# controller.net
KiCad netlist of a schematic drawn in EAGLE
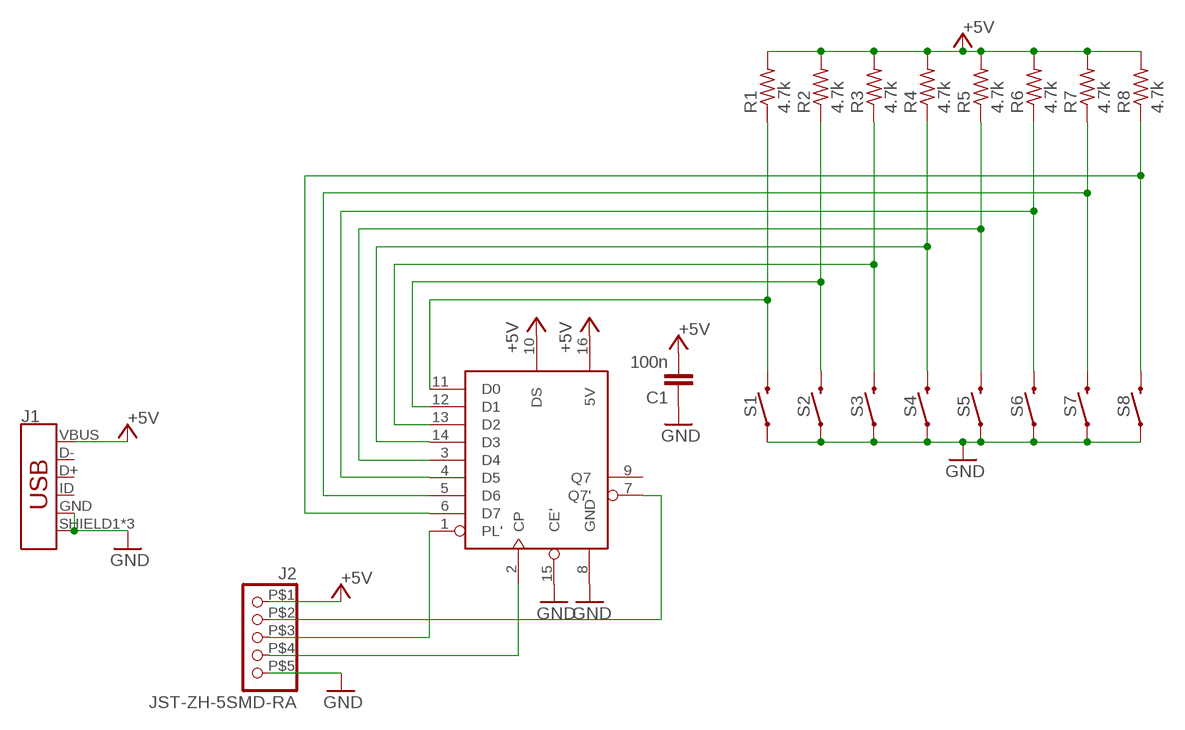
[diagram p0: schematic, sheet 1]

(export (version "E")
  (design (tool "Eeschema 10.0.6"))
  (components
    (comp (ref "C1")
      (value "100n")
      (footprint "eagle-import:C0603")
      (libsource (lib "eagle-import") (part "C-EUC0603"))
    )
    (comp (ref "J1")
      (value "USB_MICRO-B_FEMALE-SMT")
      (footprint "eagle-import:USB-B-MICRO-SMD")
      (libsource (lib "eagle-import") (part "USB_MICRO-B_FEMALE-SMT"))
    )
    (comp (ref "J2")
      (value "JST-ZH-5SMD-RA")
      (footprint "eagle-import:JST-ZH-5-SMD-RA")
      (libsource (lib "eagle-import") (part "JST-ZH-5SMD-RA"))
    )
    (comp (ref "R1")
      (value "4.7k")
      (footprint "eagle-import:R0603")
      (libsource (lib "eagle-import") (part "R-US_R0603"))
    )
    (comp (ref "R2")
      (value "4.7k")
      (footprint "eagle-import:R0603")
      (libsource (lib "eagle-import") (part "R-US_R0603"))
    )
    (comp (ref "R3")
      (value "4.7k")
      (footprint "eagle-import:R0603")
      (libsource (lib "eagle-import") (part "R-US_R0603"))
    )
    (comp (ref "R4")
      (value "4.7k")
      (footprint "eagle-import:R0603")
      (libsource (lib "eagle-import") (part "R-US_R0603"))
    )
    (comp (ref "R5")
      (value "4.7k")
      (footprint "eagle-import:R0603")
      (libsource (lib "eagle-import") (part "R-US_R0603"))
    )
    (comp (ref "R6")
      (value "4.7k")
      (footprint "eagle-import:R0603")
      (libsource (lib "eagle-import") (part "R-US_R0603"))
    )
    (comp (ref "R7")
      (value "4.7k")
      (footprint "eagle-import:R0603")
      (libsource (lib "eagle-import") (part "R-US_R0603"))
    )
    (comp (ref "R8")
      (value "4.7k")
      (footprint "eagle-import:R0603")
      (libsource (lib "eagle-import") (part "R-US_R0603"))
    )
    (comp (ref "S1")
      (value "MOMENTARY-SWITCH-SPST-SMD-6.0X3.5MM")
      (footprint "eagle-import:TACTILE_SWITCH_SMD_6.0X3.5MM")
      (libsource (lib "eagle-import") (part "MOMENTARY-SWITCH-SPST-SMD-6.0X3.5MM"))
    )
    (comp (ref "S2")
      (value "MOMENTARY-SWITCH-SPST-SMD-6.0X3.5MM")
      (footprint "eagle-import:TACTILE_SWITCH_SMD_6.0X3.5MM")
      (libsource (lib "eagle-import") (part "MOMENTARY-SWITCH-SPST-SMD-6.0X3.5MM"))
    )
    (comp (ref "S3")
      (value "MOMENTARY-SWITCH-SPST-SMD-6.0X3.5MM")
      (footprint "eagle-import:TACTILE_SWITCH_SMD_6.0X3.5MM")
      (libsource (lib "eagle-import") (part "MOMENTARY-SWITCH-SPST-SMD-6.0X3.5MM"))
    )
    (comp (ref "S4")
      (value "MOMENTARY-SWITCH-SPST-SMD-6.0X3.5MM")
      (footprint "eagle-import:TACTILE_SWITCH_SMD_6.0X3.5MM")
      (libsource (lib "eagle-import") (part "MOMENTARY-SWITCH-SPST-SMD-6.0X3.5MM"))
    )
    (comp (ref "S5")
      (value "MOMENTARY-SWITCH-SPST-SMD-6.0X3.5MM")
      (footprint "eagle-import:TACTILE_SWITCH_SMD_6.0X3.5MM")
      (libsource (lib "eagle-import") (part "MOMENTARY-SWITCH-SPST-SMD-6.0X3.5MM"))
    )
    (comp (ref "S6")
      (value "MOMENTARY-SWITCH-SPST-SMD-6.0X3.5MM")
      (footprint "eagle-import:TACTILE_SWITCH_SMD_6.0X3.5MM")
      (libsource (lib "eagle-import") (part "MOMENTARY-SWITCH-SPST-SMD-6.0X3.5MM"))
    )
    (comp (ref "S7")
      (value "MOMENTARY-SWITCH-SPST-SMD-6.0X3.5MM")
      (footprint "eagle-import:TACTILE_SWITCH_SMD_6.0X3.5MM")
      (libsource (lib "eagle-import") (part "MOMENTARY-SWITCH-SPST-SMD-6.0X3.5MM"))
    )
    (comp (ref "S8")
      (value "MOMENTARY-SWITCH-SPST-SMD-6.0X3.5MM")
      (footprint "eagle-import:TACTILE_SWITCH_SMD_6.0X3.5MM")
      (libsource (lib "eagle-import") (part "MOMENTARY-SWITCH-SPST-SMD-6.0X3.5MM"))
    )
    (comp (ref "U1")
      (value "74HCT165TSSOP16")
      (footprint "eagle-import:SOP65P640X110-16N")
      (libsource (lib "eagle-import") (part "74HCT165TSSOP16"))
    )
  )
  (nets
    (net (code "1") (name "+5V") (class "Default")
      (node (ref "C1") (pin "2") (pinfunction "2_2") (pintype "passive"))
      (node (ref "J1") (pin "VBUS") (pinfunction "VBUS_VBUS") (pintype "power_in"))
      (node (ref "J2") (pin "P$1") (pinfunction "1_P$1") (pintype "passive"))
      (node (ref "R1") (pin "2") (pinfunction "2_2") (pintype "passive"))
      (node (ref "R2") (pin "2") (pinfunction "2_2") (pintype "passive"))
      (node (ref "R3") (pin "2") (pinfunction "2_2") (pintype "passive"))
      (node (ref "R4") (pin "2") (pinfunction "2_2") (pintype "passive"))
      (node (ref "R5") (pin "2") (pinfunction "2_2") (pintype "passive"))
      (node (ref "R6") (pin "2") (pinfunction "2_2") (pintype "passive"))
      (node (ref "R7") (pin "2") (pinfunction "2_2") (pintype "passive"))
      (node (ref "R8") (pin "2") (pinfunction "2_2") (pintype "passive"))
      (node (ref "U1") (pin "10") (pinfunction "DS_10") (pintype "input"))
      (node (ref "U1") (pin "16") (pinfunction "5V_16") (pintype "power_in"))
    )
    (net (code "2") (name "GND") (class "Default")
      (node (ref "C1") (pin "1") (pinfunction "1_1") (pintype "passive"))
      (node (ref "J1") (pin "GND") (pinfunction "GND_GND") (pintype "power_in"))
      (node (ref "J1") (pin "SHIELD1") (pinfunction "SHIELD_SHIELD1") (pintype "bidirectional"))
      (node (ref "J1") (pin "SHIELD2") (pinfunction "SHIELD_SHIELD2") (pintype "bidirectional"))
      (node (ref "J1") (pin "SHIELD3") (pinfunction "SHIELD_SHIELD3") (pintype "bidirectional"))
      (node (ref "J2") (pin "P$5") (pinfunction "5_P$5") (pintype "passive"))
      (node (ref "S1") (pin "1") (pinfunction "1_1") (pintype "passive"))
      (node (ref "S2") (pin "1") (pinfunction "1_1") (pintype "passive"))
      (node (ref "S3") (pin "1") (pinfunction "1_1") (pintype "passive"))
      (node (ref "S4") (pin "1") (pinfunction "1_1") (pintype "passive"))
      (node (ref "S5") (pin "1") (pinfunction "1_1") (pintype "passive"))
      (node (ref "S6") (pin "1") (pinfunction "1_1") (pintype "passive"))
      (node (ref "S7") (pin "1") (pinfunction "1_1") (pintype "passive"))
      (node (ref "S8") (pin "1") (pinfunction "1_1") (pintype "passive"))
      (node (ref "U1") (pin "15") (pinfunction "CE'_15") (pintype "input"))
      (node (ref "U1") (pin "8") (pinfunction "GND_8") (pintype "power_in"))
    )
    (net (code "3") (name "Net-(J2-2)") (class "Default")
      (node (ref "J2") (pin "P$2") (pinfunction "2_P$2") (pintype "passive"))
      (node (ref "U1") (pin "7") (pinfunction "Q7'_7") (pintype "output"))
    )
    (net (code "4") (name "Net-(J2-3)") (class "Default")
      (node (ref "J2") (pin "P$3") (pinfunction "3_P$3") (pintype "passive"))
      (node (ref "U1") (pin "1") (pinfunction "PL'_1") (pintype "input"))
    )
    (net (code "5") (name "Net-(J2-4)") (class "Default")
      (node (ref "J2") (pin "P$4") (pinfunction "4_P$4") (pintype "passive"))
      (node (ref "U1") (pin "2") (pinfunction "CP_2") (pintype "input"))
    )
    (net (code "6") (name "Net-(U1-D0)") (class "Default")
      (node (ref "R1") (pin "1") (pinfunction "1_1") (pintype "passive"))
      (node (ref "S1") (pin "2") (pinfunction "2_2") (pintype "passive"))
      (node (ref "U1") (pin "11") (pinfunction "D0_11") (pintype "input"))
    )
    (net (code "7") (name "Net-(U1-D1)") (class "Default")
      (node (ref "R2") (pin "1") (pinfunction "1_1") (pintype "passive"))
      (node (ref "S2") (pin "2") (pinfunction "2_2") (pintype "passive"))
      (node (ref "U1") (pin "12") (pinfunction "D1_12") (pintype "input"))
    )
    (net (code "8") (name "Net-(U1-D2)") (class "Default")
      (node (ref "R3") (pin "1") (pinfunction "1_1") (pintype "passive"))
      (node (ref "S3") (pin "2") (pinfunction "2_2") (pintype "passive"))
      (node (ref "U1") (pin "13") (pinfunction "D2_13") (pintype "input"))
    )
    (net (code "9") (name "Net-(U1-D3)") (class "Default")
      (node (ref "R4") (pin "1") (pinfunction "1_1") (pintype "passive"))
      (node (ref "S4") (pin "2") (pinfunction "2_2") (pintype "passive"))
      (node (ref "U1") (pin "14") (pinfunction "D3_14") (pintype "input"))
    )
    (net (code "10") (name "Net-(U1-D4)") (class "Default")
      (node (ref "R5") (pin "1") (pinfunction "1_1") (pintype "passive"))
      (node (ref "S5") (pin "2") (pinfunction "2_2") (pintype "passive"))
      (node (ref "U1") (pin "3") (pinfunction "D4_3") (pintype "input"))
    )
    (net (code "11") (name "Net-(U1-D5)") (class "Default")
      (node (ref "R6") (pin "1") (pinfunction "1_1") (pintype "passive"))
      (node (ref "S6") (pin "2") (pinfunction "2_2") (pintype "passive"))
      (node (ref "U1") (pin "4") (pinfunction "D5_4") (pintype "input"))
    )
    (net (code "12") (name "Net-(U1-D6)") (class "Default")
      (node (ref "R7") (pin "1") (pinfunction "1_1") (pintype "passive"))
      (node (ref "S7") (pin "2") (pinfunction "2_2") (pintype "passive"))
      (node (ref "U1") (pin "5") (pinfunction "D6_5") (pintype "input"))
    )
    (net (code "13") (name "Net-(U1-D7)") (class "Default")
      (node (ref "R8") (pin "1") (pinfunction "1_1") (pintype "passive"))
      (node (ref "S8") (pin "2") (pinfunction "2_2") (pintype "passive"))
      (node (ref "U1") (pin "6") (pinfunction "D7_6") (pintype "input"))
    )
    (net (code "14") (name "unconnected-(J1-PadD+)") (class "Default")
      (node (ref "J1") (pin "D+") (pinfunction "D+_D+") (pintype "bidirectional"))
    )
    (net (code "15") (name "unconnected-(J1-PadD-)") (class "Default")
      (node (ref "J1") (pin "D-") (pinfunction "D-_D-") (pintype "bidirectional"))
    )
    (net (code "16") (name "unconnected-(J1-PadID)") (class "Default")
      (node (ref "J1") (pin "ID") (pinfunction "ID_ID") (pintype "bidirectional"))
    )
    (net (code "17") (name "unconnected-(U1-Q7-Pad9)") (class "Default")
      (node (ref "U1") (pin "9") (pinfunction "Q7_9") (pintype "output"))
    )
  )
)
